# INPUTS_OUTPUTS.net
KiCad netlist of a schematic drawn in Altium Designer
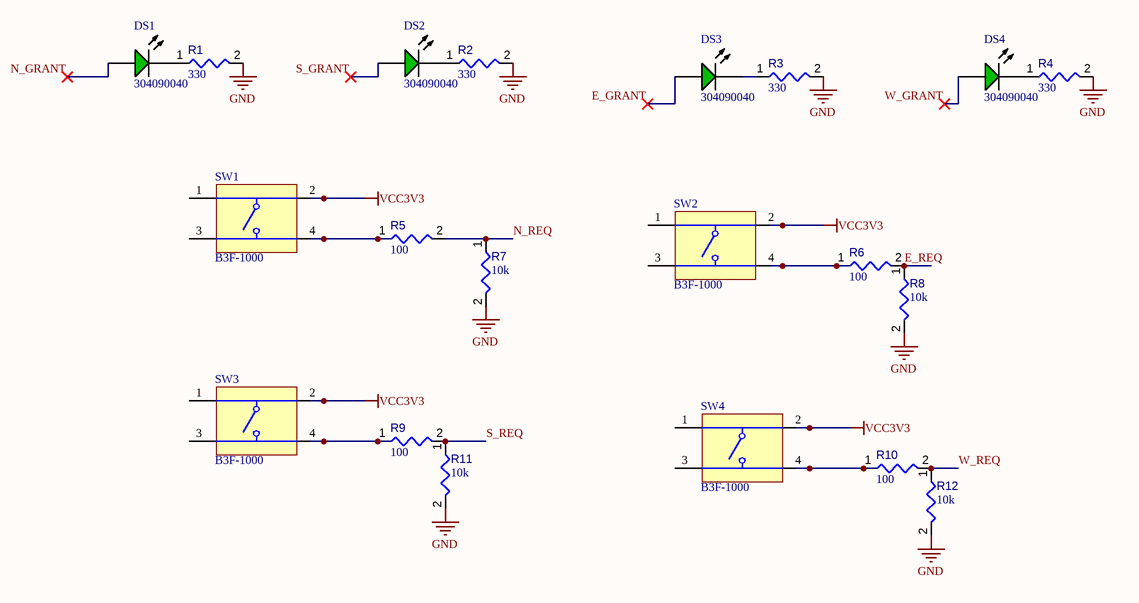
[diagram p0: INPUTS_OUTPUTS.SchDoc]

(export (version "E")
  (design (tool "Eeschema 10.0.6"))
  (components
    (comp (ref "DS1")
      (value "304090040")
      (footprint "LED-2P-2.28-3MM")
      (description "Green LED, 80 mW, 20 mA, -25 to 85 degC, 2-Pin THD")
      (fields (field (name "MANUFACTURER") "Shenzhen CGX"))
      (libsource (lib "Md-azadul Islam") (part "LED-GREEN-AK-2"))
    )
    (comp (ref "DS2")
      (value "304090040")
      (footprint "LED-2P-2.28-3MM")
      (description "Green LED, 80 mW, 20 mA, -25 to 85 degC, 2-Pin THD")
      (fields (field (name "MANUFACTURER") "Shenzhen CGX"))
      (libsource (lib "Md-azadul Islam") (part "LED-GREEN-AK-2"))
    )
    (comp (ref "DS3")
      (value "304090040")
      (footprint "LED-2P-2.28-3MM")
      (description "Green LED, 80 mW, 20 mA, -25 to 85 degC, 2-Pin THD")
      (fields (field (name "MANUFACTURER") "Shenzhen CGX"))
      (libsource (lib "Md-azadul Islam") (part "LED-GREEN-AK-2"))
    )
    (comp (ref "DS4")
      (value "304090040")
      (footprint "LED-2P-2.28-3MM")
      (description "Green LED, 80 mW, 20 mA, -25 to 85 degC, 2-Pin THD")
      (fields (field (name "MANUFACTURER") "Shenzhen CGX"))
      (libsource (lib "Md-azadul Islam") (part "LED-GREEN-AK-2"))
    )
    (comp (ref "R1")
      (value "330")
      (footprint "RESC0402(1005)_L")
      (description "Chip Resistor, 330 Ohms, +/-5 %, 63 mW, -55 to 155 degC, 0402")
      (fields (field (name "POWER") "63mW") (field (name "TOLERANCE") "5%"))
      (libsource (lib "Md-azadul Islam") (part "RES-2"))
    )
    (comp (ref "R2")
      (value "330")
      (footprint "RESC0402(1005)_L")
      (description "Chip Resistor, 330 Ohms, +/-5 %, 63 mW, -55 to 155 degC, 0402")
      (fields (field (name "POWER") "63mW") (field (name "TOLERANCE") "5%"))
      (libsource (lib "Md-azadul Islam") (part "RES-2"))
    )
    (comp (ref "R3")
      (value "330")
      (footprint "RESC0402(1005)_L")
      (description "Chip Resistor, 330 Ohms, +/-5 %, 63 mW, -55 to 155 degC, 0402")
      (fields (field (name "POWER") "63mW") (field (name "TOLERANCE") "5%"))
      (libsource (lib "Md-azadul Islam") (part "RES-2"))
    )
    (comp (ref "R4")
      (value "330")
      (footprint "RESC0402(1005)_L")
      (description "Chip Resistor, 330 Ohms, +/-5 %, 63 mW, -55 to 155 degC, 0402")
      (fields (field (name "POWER") "63mW") (field (name "TOLERANCE") "5%"))
      (libsource (lib "Md-azadul Islam") (part "RES-2"))
    )
    (comp (ref "R5")
      (value "100")
      (footprint "RESC0402(1005)_L")
      (description "100R 0.063W 1% 0402 (1005 Metric)  SMD")
      (fields (field (name "TOLERANCE") "1%") (field (name "POWER") "63mW"))
      (libsource (lib "Md-azadul Islam") (part "100R2F"))
    )
    (comp (ref "R6")
      (value "100")
      (footprint "RESC0402(1005)_L")
      (description "100R 0.063W 1% 0402 (1005 Metric)  SMD")
      (fields (field (name "TOLERANCE") "1%") (field (name "POWER") "63mW"))
      (libsource (lib "Md-azadul Islam") (part "100R2F"))
    )
    (comp (ref "R7")
      (value "10k")
      (footprint "RESC0402(1005)_L")
      (description "10K 0.063W 1% 0402 (1005 Metric)  SMD")
      (fields (field (name "POWER") "63mW") (field (name "TOLERANCE") "1%"))
      (libsource (lib "Md-azadul Islam") (part "10KR2F"))
    )
    (comp (ref "R8")
      (value "10k")
      (footprint "RESC0402(1005)_L")
      (description "10K 0.063W 1% 0402 (1005 Metric)  SMD")
      (fields (field (name "POWER") "63mW") (field (name "TOLERANCE") "1%"))
      (libsource (lib "Md-azadul Islam") (part "10KR2F"))
    )
    (comp (ref "R9")
      (value "100")
      (footprint "RESC0402(1005)_L")
      (description "100R 0.063W 1% 0402 (1005 Metric)  SMD")
      (fields (field (name "TOLERANCE") "1%") (field (name "POWER") "63mW"))
      (libsource (lib "Md-azadul Islam") (part "100R2F"))
    )
    (comp (ref "R10")
      (value "100")
      (footprint "RESC0402(1005)_L")
      (description "100R 0.063W 1% 0402 (1005 Metric)  SMD")
      (fields (field (name "TOLERANCE") "1%") (field (name "POWER") "63mW"))
      (libsource (lib "Md-azadul Islam") (part "100R2F"))
    )
    (comp (ref "R11")
      (value "10k")
      (footprint "RESC0402(1005)_L")
      (description "10K 0.063W 1% 0402 (1005 Metric)  SMD")
      (fields (field (name "POWER") "63mW") (field (name "TOLERANCE") "1%"))
      (libsource (lib "Md-azadul Islam") (part "10KR2F"))
    )
    (comp (ref "R12")
      (value "10k")
      (footprint "RESC0402(1005)_L")
      (description "10K 0.063W 1% 0402 (1005 Metric)  SMD")
      (fields (field (name "POWER") "63mW") (field (name "TOLERANCE") "1%"))
      (libsource (lib "Md-azadul Islam") (part "10KR2F"))
    )
    (comp (ref "SW1")
      (value "B3F-1000")
      (footprint "OMRON-B3F-1000-4_V")
      (description "Tactile Switch, SPST-NO, 0.05 A, 24 V, -25 to 70 degC, 4-Pin THD, RoHS, Bulk")
      (fields (field (name "MANUFACTURER") "Omron Electronic Components"))
      (libsource (lib "Md-azadul Islam") (part "SW-SPST-4_A"))
    )
    (comp (ref "SW2")
      (value "B3F-1000")
      (footprint "OMRON-B3F-1000-4_V")
      (description "Tactile Switch, SPST-NO, 0.05 A, 24 V, -25 to 70 degC, 4-Pin THD, RoHS, Bulk")
      (fields (field (name "MANUFACTURER") "Omron Electronic Components"))
      (libsource (lib "Md-azadul Islam") (part "SW-SPST-4_A"))
    )
    (comp (ref "SW3")
      (value "B3F-1000")
      (footprint "OMRON-B3F-1000-4_V")
      (description "Tactile Switch, SPST-NO, 0.05 A, 24 V, -25 to 70 degC, 4-Pin THD, RoHS, Bulk")
      (fields (field (name "MANUFACTURER") "Omron Electronic Components"))
      (libsource (lib "Md-azadul Islam") (part "SW-SPST-4_A"))
    )
    (comp (ref "SW4")
      (value "B3F-1000")
      (footprint "OMRON-B3F-1000-4_V")
      (description "Tactile Switch, SPST-NO, 0.05 A, 24 V, -25 to 70 degC, 4-Pin THD, RoHS, Bulk")
      (fields (field (name "MANUFACTURER") "Omron Electronic Components"))
      (libsource (lib "Md-azadul Islam") (part "SW-SPST-4_A"))
    )
  )
  (nets
    (net (code "1") (name "/E_GRANT") (class "Default")
      (node (ref "DS3") (pin "1") (pinfunction "A_1") (pintype "passive+no_connect"))
    )
    (net (code "2") (name "/E_REQ") (class "Default")
      (node (ref "R6") (pin "2") (pinfunction "2_2") (pintype "passive"))
      (node (ref "R8") (pin "1") (pinfunction "1_1") (pintype "passive"))
    )
    (net (code "3") (name "/N_GRANT") (class "Default")
      (node (ref "DS1") (pin "1") (pinfunction "A_1") (pintype "passive+no_connect"))
    )
    (net (code "4") (name "/N_REQ") (class "Default")
      (node (ref "R5") (pin "2") (pinfunction "2_2") (pintype "passive"))
      (node (ref "R7") (pin "1") (pinfunction "1_1") (pintype "passive"))
    )
    (net (code "5") (name "/S_GRANT") (class "Default")
      (node (ref "DS2") (pin "1") (pinfunction "A_1") (pintype "passive+no_connect"))
    )
    (net (code "6") (name "/S_REQ") (class "Default")
      (node (ref "R11") (pin "1") (pinfunction "1_1") (pintype "passive"))
      (node (ref "R9") (pin "2") (pinfunction "2_2") (pintype "passive"))
    )
    (net (code "7") (name "/W_GRANT") (class "Default")
      (node (ref "DS4") (pin "1") (pinfunction "A_1") (pintype "passive+no_connect"))
    )
    (net (code "8") (name "/W_REQ") (class "Default")
      (node (ref "R10") (pin "2") (pinfunction "2_2") (pintype "passive"))
      (node (ref "R12") (pin "1") (pinfunction "1_1") (pintype "passive"))
    )
    (net (code "9") (name "GND") (class "Default")
      (node (ref "R1") (pin "2") (pinfunction "2_2") (pintype "passive"))
      (node (ref "R11") (pin "2") (pinfunction "2_2") (pintype "passive"))
      (node (ref "R12") (pin "2") (pinfunction "2_2") (pintype "passive"))
      (node (ref "R2") (pin "2") (pinfunction "2_2") (pintype "passive"))
      (node (ref "R3") (pin "2") (pinfunction "2_2") (pintype "passive"))
      (node (ref "R4") (pin "2") (pinfunction "2_2") (pintype "passive"))
      (node (ref "R7") (pin "2") (pinfunction "2_2") (pintype "passive"))
      (node (ref "R8") (pin "2") (pinfunction "2_2") (pintype "passive"))
    )
    (net (code "10") (name "Net-(DS1-K)") (class "Default")
      (node (ref "DS1") (pin "2") (pinfunction "K_2") (pintype "passive"))
      (node (ref "R1") (pin "1") (pinfunction "1_1") (pintype "passive"))
    )
    (net (code "11") (name "Net-(DS2-K)") (class "Default")
      (node (ref "DS2") (pin "2") (pinfunction "K_2") (pintype "passive"))
      (node (ref "R2") (pin "1") (pinfunction "1_1") (pintype "passive"))
    )
    (net (code "12") (name "Net-(DS3-K)") (class "Default")
      (node (ref "DS3") (pin "2") (pinfunction "K_2") (pintype "passive"))
      (node (ref "R3") (pin "1") (pinfunction "1_1") (pintype "passive"))
    )
    (net (code "13") (name "Net-(DS4-K)") (class "Default")
      (node (ref "DS4") (pin "2") (pinfunction "K_2") (pintype "passive"))
      (node (ref "R4") (pin "1") (pinfunction "1_1") (pintype "passive"))
    )
    (net (code "14") (name "Net-(R5-Pad1)") (class "Default")
      (node (ref "R5") (pin "1") (pinfunction "1_1") (pintype "passive"))
      (node (ref "SW1") (pin "4") (pinfunction "4_4") (pintype "passive"))
    )
    (net (code "15") (name "Net-(R6-Pad1)") (class "Default")
      (node (ref "R6") (pin "1") (pinfunction "1_1") (pintype "passive"))
      (node (ref "SW2") (pin "4") (pinfunction "4_4") (pintype "passive"))
    )
    (net (code "16") (name "Net-(R9-Pad1)") (class "Default")
      (node (ref "R9") (pin "1") (pinfunction "1_1") (pintype "passive"))
      (node (ref "SW3") (pin "4") (pinfunction "4_4") (pintype "passive"))
    )
    (net (code "17") (name "Net-(R10-Pad1)") (class "Default")
      (node (ref "R10") (pin "1") (pinfunction "1_1") (pintype "passive"))
      (node (ref "SW4") (pin "4") (pinfunction "4_4") (pintype "passive"))
    )
    (net (code "18") (name "VCC3V3") (class "Default")
      (node (ref "SW1") (pin "2") (pinfunction "2_2") (pintype "passive"))
      (node (ref "SW2") (pin "2") (pinfunction "2_2") (pintype "passive"))
      (node (ref "SW3") (pin "2") (pinfunction "2_2") (pintype "passive"))
      (node (ref "SW4") (pin "2") (pinfunction "2_2") (pintype "passive"))
    )
    (net (code "19") (name "unconnected-(SW1-Pad1)") (class "Default")
      (node (ref "SW1") (pin "1") (pinfunction "1_1") (pintype "passive"))
    )
    (net (code "20") (name "unconnected-(SW1-Pad3)") (class "Default")
      (node (ref "SW1") (pin "3") (pinfunction "3_3") (pintype "passive"))
    )
    (net (code "21") (name "unconnected-(SW2-Pad1)") (class "Default")
      (node (ref "SW2") (pin "1") (pinfunction "1_1") (pintype "passive"))
    )
    (net (code "22") (name "unconnected-(SW2-Pad3)") (class "Default")
      (node (ref "SW2") (pin "3") (pinfunction "3_3") (pintype "passive"))
    )
    (net (code "23") (name "unconnected-(SW3-Pad1)") (class "Default")
      (node (ref "SW3") (pin "1") (pinfunction "1_1") (pintype "passive"))
    )
    (net (code "24") (name "unconnected-(SW3-Pad3)") (class "Default")
      (node (ref "SW3") (pin "3") (pinfunction "3_3") (pintype "passive"))
    )
    (net (code "25") (name "unconnected-(SW4-Pad1)") (class "Default")
      (node (ref "SW4") (pin "1") (pinfunction "1_1") (pintype "passive"))
    )
    (net (code "26") (name "unconnected-(SW4-Pad3)") (class "Default")
      (node (ref "SW4") (pin "3") (pinfunction "3_3") (pintype "passive"))
    )
  )
)
